# DM1097_BootSel.net
KiCad netlist of a schematic drawn in Altium Designer
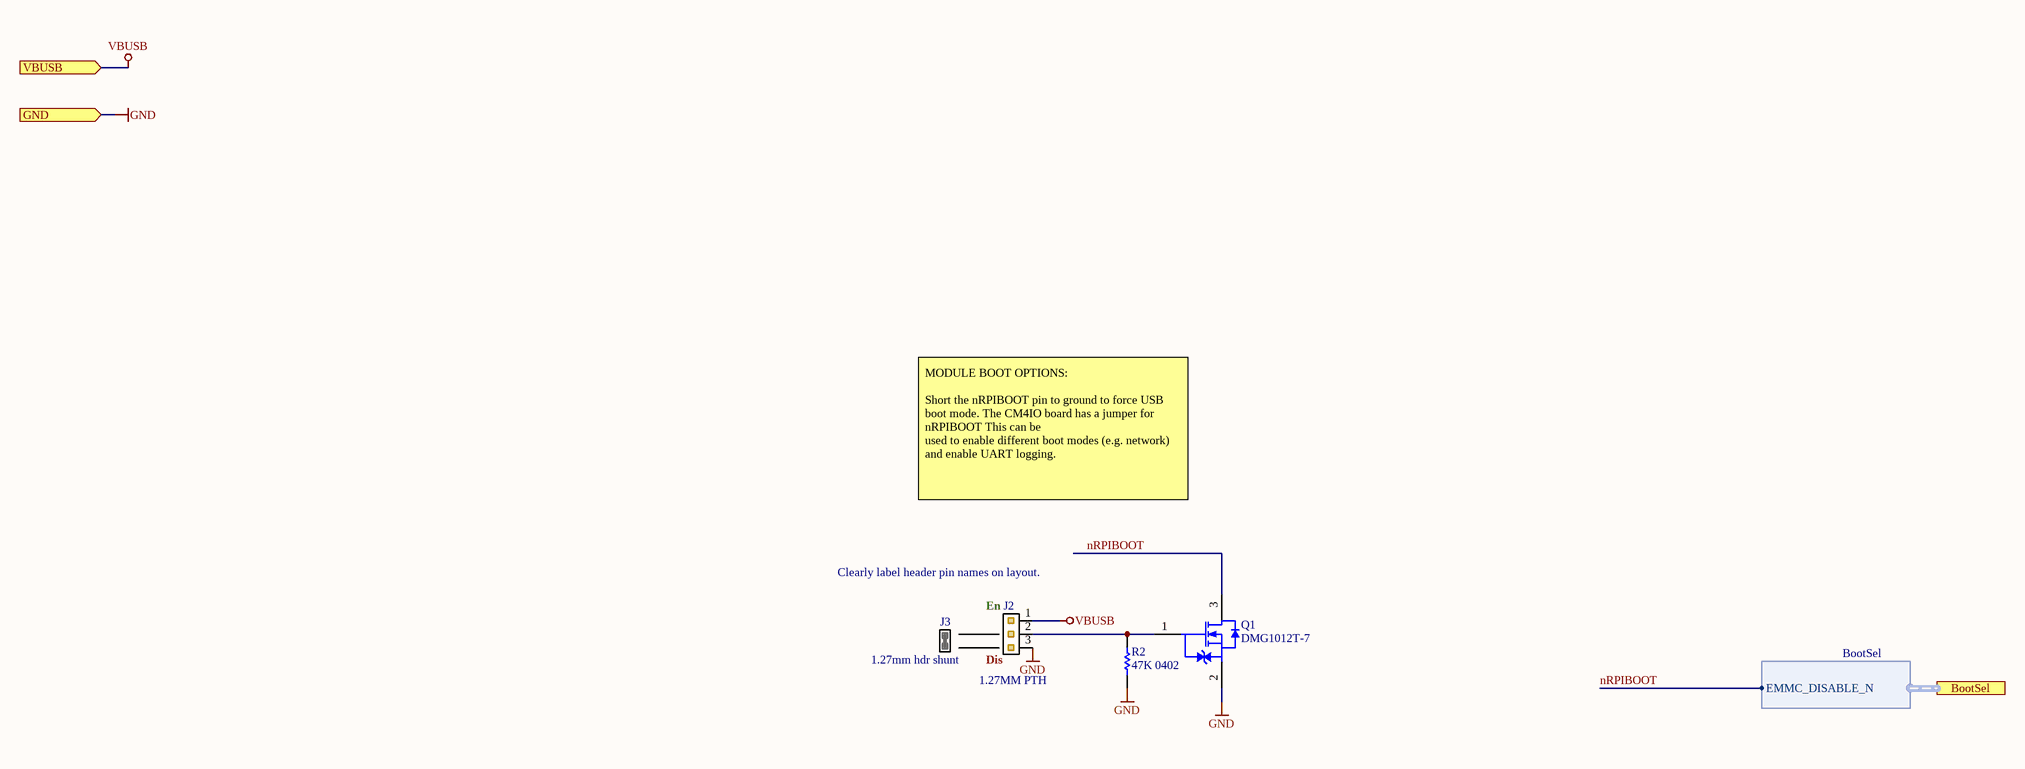
[diagram p0: DM1097_BootSel.SchDoc]

(export (version "E")
  (design (tool "Eeschema 10.0.6"))
  (components
    (comp (ref "J2")
      (value "1.27MM PTH")
      (footprint "LuxonisMaster:GRPB031VWVN-RC")
      (description "CONN HEADER VERT 3POS 1.27MM")
      (libsource (lib "LuxonisMaster") (part "GRPB031VWVN-RC"))
    )
    (comp (ref "J3")
      (value "1.27mm hdr shunt")
      (footprint "LuxonisMaster:M50-1900005")
      (description "CONN SHUNT 1.27MM BLACK")
      (libsource (lib "LuxonisMaster") (part "M50-1900005"))
    )
    (comp (ref "Q1")
      (value "DMG1012T-7")
      (footprint "LuxonisMaster:DMG1012T-7")
      (description "MOSFET N-CH 20V 630MA SOT-523")
      (libsource (lib "LuxonisMaster") (part "DMG1012T-7"))
    )
    (comp (ref "R2")
      (value "47K 0402")
      (footprint "RES_Altium_Vault_Generic:RESC0402(1005)_N")
      (description "RES SMD 47K OHM 1% 1/16W 0402")
      (fields (field (name "TOLERANCE") "1%"))
      (libsource (lib "LuxonisMaster") (part "RC0402FR-0747KL"))
    )
  )
  (nets
    (net (code "2") (name "/nRPIBOOT") (class "Default")
      (node (ref "Q1") (pin "3") (pinfunction "3_3") (pintype "passive"))
    )
    (net (code "4") (name "GND") (class "Default")
      (node (ref "J2") (pin "3") (pinfunction "3_3") (pintype "passive"))
      (node (ref "Q1") (pin "2") (pinfunction "2_2") (pintype "passive"))
      (node (ref "R2") (pin "1") (pinfunction "1_1") (pintype "passive"))
    )
    (net (code "5") (name "Net-(J2-Pad2)") (class "Default")
      (node (ref "J2") (pin "2") (pinfunction "2_2") (pintype "passive"))
      (node (ref "Q1") (pin "1") (pinfunction "1_1") (pintype "passive"))
      (node (ref "R2") (pin "2") (pinfunction "2_2") (pintype "passive"))
    )
    (net (code "6") (name "VBUSB") (class "Default")
      (node (ref "J2") (pin "1") (pinfunction "1_1") (pintype "passive"))
    )
  )
)
